# PWM_OUTPUT.net
KiCad netlist of a schematic drawn in Altium Designer
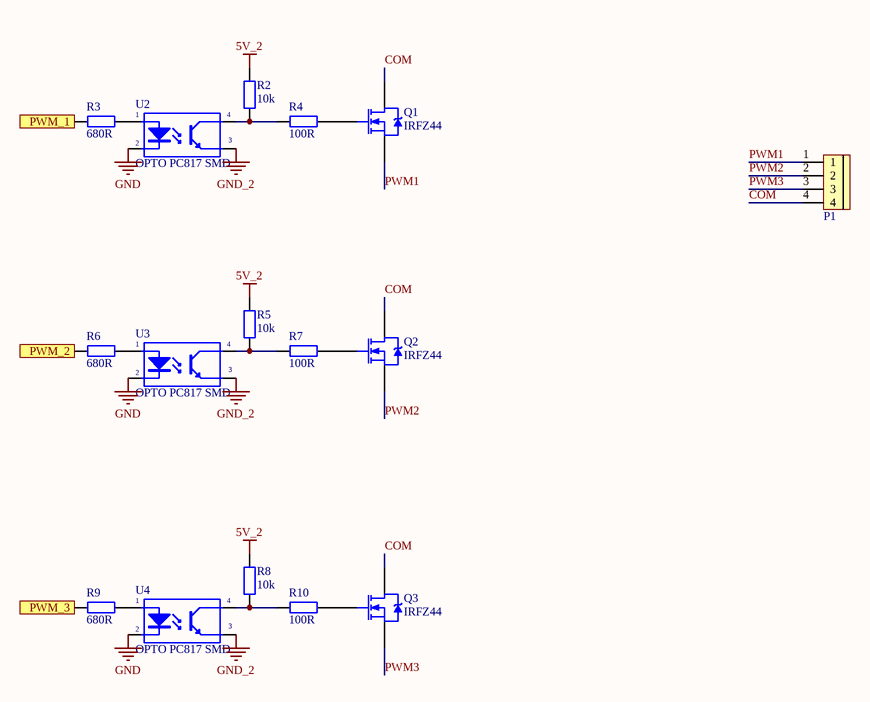
[diagram p0: PWM_OUTPUT.SchDoc]

(export (version "E")
  (design (tool "Eeschema 10.0.6"))
  (components
    (comp (ref "P1")
      (value "CON 4 EDG5.08")
      (footprint "CON 4 4EDG5.08")
      (description "Cắm")
      (libsource (lib "Altium_Lib_by_KhueNguyenCreator") (part "CON 4 EDG5.08"))
    )
    (comp (ref "Q1")
      (value "IRFZ44")
      (footprint "TO220")
      (description "N-Channel Power MOSFET")
      (libsource (lib "Altium_Lib_by_KhueNguyenCreator") (part "IRFZ44 DIP"))
    )
    (comp (ref "Q2")
      (value "IRFZ44")
      (footprint "TO220")
      (description "N-Channel Power MOSFET")
      (libsource (lib "Altium_Lib_by_KhueNguyenCreator") (part "IRFZ44 DIP"))
    )
    (comp (ref "Q3")
      (value "IRFZ44")
      (footprint "TO220")
      (description "N-Channel Power MOSFET")
      (libsource (lib "Altium_Lib_by_KhueNguyenCreator") (part "IRFZ44 DIP"))
    )
    (comp (ref "R2")
      (value "10k")
      (footprint "tro smd 0603")
      (description "Dán")
      (libsource (lib "Altium_Lib_by_KhueNguyenCreator") (part "Tro 0603 5% 10k"))
    )
    (comp (ref "R3")
      (value "680R")
      (footprint "tro smd 0603")
      (description "Dán")
      (libsource (lib "Altium_Lib_by_KhueNguyenCreator") (part "Tro 0603 1% 680R"))
    )
    (comp (ref "R4")
      (value "100R")
      (footprint "tro smd 0603")
      (description "Dán")
      (libsource (lib "Altium_Lib_by_KhueNguyenCreator") (part "Tro 0603 5% 100R"))
    )
    (comp (ref "R5")
      (value "10k")
      (footprint "tro smd 0603")
      (description "Dán")
      (libsource (lib "Altium_Lib_by_KhueNguyenCreator") (part "Tro 0603 5% 10k"))
    )
    (comp (ref "R6")
      (value "680R")
      (footprint "tro smd 0603")
      (description "Dán")
      (libsource (lib "Altium_Lib_by_KhueNguyenCreator") (part "Tro 0603 1% 680R"))
    )
    (comp (ref "R7")
      (value "100R")
      (footprint "tro smd 0603")
      (description "Dán")
      (libsource (lib "Altium_Lib_by_KhueNguyenCreator") (part "Tro 0603 5% 100R"))
    )
    (comp (ref "R8")
      (value "10k")
      (footprint "tro smd 0603")
      (description "Dán")
      (libsource (lib "Altium_Lib_by_KhueNguyenCreator") (part "Tro 0603 5% 10k"))
    )
    (comp (ref "R9")
      (value "680R")
      (footprint "tro smd 0603")
      (description "Dán")
      (libsource (lib "Altium_Lib_by_KhueNguyenCreator") (part "Tro 0603 1% 680R"))
    )
    (comp (ref "R10")
      (value "100R")
      (footprint "tro smd 0603")
      (description "Dán")
      (libsource (lib "Altium_Lib_by_KhueNguyenCreator") (part "Tro 0603 5% 100R"))
    )
    (comp (ref "U2")
      (value "OPTO PC817 SMD")
      (footprint "SOP4")
      (description "Single Opto")
      (libsource (lib "Altium_Lib_by_KhueNguyenCreator") (part "OPTO PC817 SMD"))
    )
    (comp (ref "U3")
      (value "OPTO PC817 SMD")
      (footprint "SOP4")
      (description "Single Opto")
      (libsource (lib "Altium_Lib_by_KhueNguyenCreator") (part "OPTO PC817 SMD"))
    )
    (comp (ref "U4")
      (value "OPTO PC817 SMD")
      (footprint "SOP4")
      (description "Single Opto")
      (libsource (lib "Altium_Lib_by_KhueNguyenCreator") (part "OPTO PC817 SMD"))
    )
  )
  (nets
    (net (code "1") (name "/COM") (class "Default")
      (node (ref "P1") (pin "4") (pinfunction "4_4") (pintype "passive"))
      (node (ref "Q1") (pin "2") (pinfunction "D_2") (pintype "passive"))
      (node (ref "Q2") (pin "2") (pinfunction "D_2") (pintype "passive"))
      (node (ref "Q3") (pin "2") (pinfunction "D_2") (pintype "passive"))
    )
    (net (code "2") (name "/PWM1") (class "Default")
      (node (ref "P1") (pin "1") (pinfunction "1_1") (pintype "passive"))
      (node (ref "Q1") (pin "3") (pinfunction "S_3") (pintype "passive"))
    )
    (net (code "3") (name "/PWM2") (class "Default")
      (node (ref "P1") (pin "2") (pinfunction "2_2") (pintype "passive"))
      (node (ref "Q2") (pin "3") (pinfunction "S_3") (pintype "passive"))
    )
    (net (code "4") (name "/PWM3") (class "Default")
      (node (ref "P1") (pin "3") (pinfunction "3_3") (pintype "passive"))
      (node (ref "Q3") (pin "3") (pinfunction "S_3") (pintype "passive"))
    )
    (net (code "5") (name "/PWM_1") (class "Default")
      (node (ref "R3") (pin "1") (pinfunction "1_1") (pintype "passive"))
    )
    (net (code "6") (name "/PWM_2") (class "Default")
      (node (ref "R6") (pin "1") (pinfunction "1_1") (pintype "passive"))
    )
    (net (code "7") (name "/PWM_3") (class "Default")
      (node (ref "R9") (pin "1") (pinfunction "1_1") (pintype "passive"))
    )
    (net (code "8") (name "5V_2") (class "Default")
      (node (ref "R2") (pin "2") (pinfunction "2_2") (pintype "passive"))
      (node (ref "R5") (pin "2") (pinfunction "2_2") (pintype "passive"))
      (node (ref "R8") (pin "2") (pinfunction "2_2") (pintype "passive"))
    )
    (net (code "9") (name "GND") (class "Default")
      (node (ref "U2") (pin "2") (pinfunction "K_2") (pintype "passive"))
      (node (ref "U3") (pin "2") (pinfunction "K_2") (pintype "passive"))
      (node (ref "U4") (pin "2") (pinfunction "K_2") (pintype "passive"))
    )
    (net (code "10") (name "GND_2") (class "Default")
      (node (ref "U2") (pin "3") (pinfunction "E_3") (pintype "passive"))
      (node (ref "U3") (pin "3") (pinfunction "E_3") (pintype "passive"))
      (node (ref "U4") (pin "3") (pinfunction "E_3") (pintype "passive"))
    )
    (net (code "11") (name "Net-(Q1-G)") (class "Default")
      (node (ref "Q1") (pin "1") (pinfunction "G_1") (pintype "passive"))
      (node (ref "R4") (pin "2") (pinfunction "2_2") (pintype "passive"))
    )
    (net (code "12") (name "Net-(Q2-G)") (class "Default")
      (node (ref "Q2") (pin "1") (pinfunction "G_1") (pintype "passive"))
      (node (ref "R7") (pin "2") (pinfunction "2_2") (pintype "passive"))
    )
    (net (code "13") (name "Net-(Q3-G)") (class "Default")
      (node (ref "Q3") (pin "1") (pinfunction "G_1") (pintype "passive"))
      (node (ref "R10") (pin "2") (pinfunction "2_2") (pintype "passive"))
    )
    (net (code "14") (name "Net-(U2-A)") (class "Default")
      (node (ref "R3") (pin "2") (pinfunction "2_2") (pintype "passive"))
      (node (ref "U2") (pin "1") (pinfunction "A_1") (pintype "passive"))
    )
    (net (code "15") (name "Net-(U2-C)") (class "Default")
      (node (ref "R2") (pin "1") (pinfunction "1_1") (pintype "passive"))
      (node (ref "R4") (pin "1") (pinfunction "1_1") (pintype "passive"))
      (node (ref "U2") (pin "4") (pinfunction "C_4") (pintype "passive"))
    )
    (net (code "16") (name "Net-(U3-A)") (class "Default")
      (node (ref "R6") (pin "2") (pinfunction "2_2") (pintype "passive"))
      (node (ref "U3") (pin "1") (pinfunction "A_1") (pintype "passive"))
    )
    (net (code "17") (name "Net-(U3-C)") (class "Default")
      (node (ref "R5") (pin "1") (pinfunction "1_1") (pintype "passive"))
      (node (ref "R7") (pin "1") (pinfunction "1_1") (pintype "passive"))
      (node (ref "U3") (pin "4") (pinfunction "C_4") (pintype "passive"))
    )
    (net (code "18") (name "Net-(U4-A)") (class "Default")
      (node (ref "R9") (pin "2") (pinfunction "2_2") (pintype "passive"))
      (node (ref "U4") (pin "1") (pinfunction "A_1") (pintype "passive"))
    )
    (net (code "19") (name "Net-(U4-C)") (class "Default")
      (node (ref "R10") (pin "1") (pinfunction "1_1") (pintype "passive"))
      (node (ref "R8") (pin "1") (pinfunction "1_1") (pintype "passive"))
      (node (ref "U4") (pin "4") (pinfunction "C_4") (pintype "passive"))
    )
  )
)
